# bpq123.net
KiCad netlist of a schematic drawn in Altium Designer
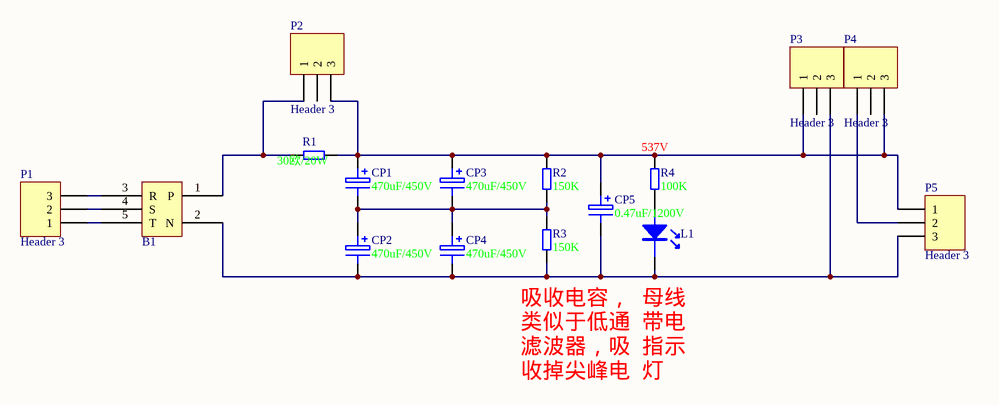
[diagram p0: bpq123.SchDoc]

(export (version "E")
  (design (tool "Eeschema 10.0.6"))
  (components
    (comp (ref "B1")
      (value "3BRIDGE")
      (footprint "cloudlib:三相整流桥")
      (libsource (lib "cloudlib") (part "三相整流桥"))
    )
    (comp (ref "CP1")
      (value "470uF/450V")
      (footprint "cloudlib:CAP_35X50")
      (description "极性电容")
      (libsource (lib "cloudlib") (part "Cap_Pol"))
    )
    (comp (ref "CP2")
      (value "470uF/450V")
      (footprint "cloudlib:CAP_35X50")
      (description "极性电容")
      (libsource (lib "cloudlib") (part "Cap_Pol"))
    )
    (comp (ref "CP3")
      (value "470uF/450V")
      (footprint "cloudlib:CAP_35X50")
      (description "极性电容")
      (libsource (lib "cloudlib") (part "Cap_Pol"))
    )
    (comp (ref "CP4")
      (value "470uF/450V")
      (footprint "cloudlib:CAP_35X50")
      (description "极性电容")
      (libsource (lib "cloudlib") (part "Cap_Pol"))
    )
    (comp (ref "CP5")
      (value "0.47uF/1200V")
      (footprint "myall:CB2")
      (description "极性电容")
      (libsource (lib "cloudlib") (part "Cap_Pol"))
    )
    (comp (ref "L1")
      (value "LED")
      (footprint "LED_1206")
      (description "发光二极管")
      (libsource (lib "cloudlib") (part "LED"))
    )
    (comp (ref "P1")
      (value "Header 3")
      (footprint "cloudlib:30A/300V")
      (description "Header, 3-Pin")
      (fields (field (name "PUBLISHER") "Altium Limited"))
      (libsource (lib "") (part "Header 3_1"))
    )
    (comp (ref "P2")
      (value "Header 3")
      (footprint "cloudlib:30A/300V")
      (description "Header, 3-Pin")
      (fields (field (name "PUBLISHER") "Altium Limited"))
      (libsource (lib "") (part "Header 3_2"))
    )
    (comp (ref "P3")
      (value "Header 3")
      (footprint "cloudlib:5.25-3")
      (description "Header, 3-Pin")
      (fields (field (name "PUBLISHER") "Altium Limited"))
      (libsource (lib "") (part "Header 3_2"))
    )
    (comp (ref "P4")
      (value "Header 3")
      (footprint "cloudlib:5.25-3")
      (description "Header, 3-Pin")
      (fields (field (name "PUBLISHER") "Altium Limited"))
      (libsource (lib "") (part "Header 3_2"))
    )
    (comp (ref "P5")
      (value "Header 3")
      (footprint "cloudlib:30A/300V")
      (description "Header, 3-Pin")
      (fields (field (name "PUBLISHER") "Altium Limited"))
      (libsource (lib "Miscellaneous Connectors") (part "Header 3"))
    )
    (comp (ref "R1")
      (value "30欧/20W")
      (footprint "cloudlib:R_30R/20W")
      (description "电阻")
      (libsource (lib "cloudlib") (part "Res"))
    )
    (comp (ref "R2")
      (value "150K")
      (footprint "myall:AXIAL0.7")
      (description "电阻")
      (libsource (lib "cloudlib") (part "Res"))
    )
    (comp (ref "R3")
      (value "150K")
      (footprint "myall:AXIAL0.7")
      (description "电阻")
      (libsource (lib "cloudlib") (part "Res"))
    )
    (comp (ref "R4")
      (value "100K")
      (footprint "myall:AXIAL0.7")
      (description "电阻")
      (libsource (lib "cloudlib") (part "Res"))
    )
  )
  (nets
    (net (code "1") (name "Net-(B1-N)") (class "Default")
      (node (ref "B1") (pin "2") (pinfunction "N_2") (pintype "passive"))
      (node (ref "CP2") (pin "2") (pinfunction "2_2") (pintype "passive"))
      (node (ref "CP4") (pin "2") (pinfunction "2_2") (pintype "passive"))
      (node (ref "CP5") (pin "2") (pinfunction "2_2") (pintype "passive"))
      (node (ref "L1") (pin "2") (pinfunction "2_2") (pintype "passive"))
      (node (ref "P3") (pin "3") (pinfunction "3_3") (pintype "passive"))
      (node (ref "P5") (pin "3") (pinfunction "3_3") (pintype "passive"))
      (node (ref "R3") (pin "1") (pinfunction "1_1") (pintype "passive"))
    )
    (net (code "2") (name "Net-(B1-P)") (class "Default")
      (node (ref "B1") (pin "1") (pinfunction "P_1") (pintype "passive"))
      (node (ref "P2") (pin "1") (pinfunction "1_1") (pintype "passive"))
      (node (ref "R1") (pin "1") (pinfunction "1_1") (pintype "passive"))
    )
    (net (code "3") (name "Net-(B1-R)") (class "Default")
      (node (ref "B1") (pin "3") (pinfunction "R_3") (pintype "passive"))
      (node (ref "P1") (pin "3") (pinfunction "3_3") (pintype "passive"))
    )
    (net (code "4") (name "Net-(B1-S)") (class "Default")
      (node (ref "B1") (pin "4") (pinfunction "S_4") (pintype "passive"))
      (node (ref "P1") (pin "2") (pinfunction "2_2") (pintype "passive"))
    )
    (net (code "5") (name "Net-(B1-T)") (class "Default")
      (node (ref "B1") (pin "5") (pinfunction "T_5") (pintype "passive"))
      (node (ref "P1") (pin "1") (pinfunction "1_1") (pintype "passive"))
    )
    (net (code "6") (name "Net-(CP1-Pad1)") (class "Default")
      (node (ref "CP1") (pin "1") (pinfunction "1_1") (pintype "passive"))
      (node (ref "CP3") (pin "1") (pinfunction "1_1") (pintype "passive"))
      (node (ref "CP5") (pin "1") (pinfunction "1_1") (pintype "passive"))
      (node (ref "P2") (pin "3") (pinfunction "3_3") (pintype "passive"))
      (node (ref "P3") (pin "1") (pinfunction "1_1") (pintype "passive"))
      (node (ref "P4") (pin "3") (pinfunction "3_3") (pintype "passive"))
      (node (ref "P5") (pin "1") (pinfunction "1_1") (pintype "passive"))
      (node (ref "R1") (pin "2") (pinfunction "2_2") (pintype "passive"))
      (node (ref "R2") (pin "2") (pinfunction "2_2") (pintype "passive"))
      (node (ref "R4") (pin "2") (pinfunction "2_2") (pintype "passive"))
    )
    (net (code "7") (name "Net-(CP1-Pad2)") (class "Default")
      (node (ref "CP1") (pin "2") (pinfunction "2_2") (pintype "passive"))
      (node (ref "CP2") (pin "1") (pinfunction "1_1") (pintype "passive"))
      (node (ref "CP3") (pin "2") (pinfunction "2_2") (pintype "passive"))
      (node (ref "CP4") (pin "1") (pinfunction "1_1") (pintype "passive"))
      (node (ref "R2") (pin "1") (pinfunction "1_1") (pintype "passive"))
      (node (ref "R3") (pin "2") (pinfunction "2_2") (pintype "passive"))
    )
    (net (code "8") (name "Net-(L1-Pad1)") (class "Default")
      (node (ref "L1") (pin "1") (pinfunction "1_1") (pintype "passive"))
      (node (ref "R4") (pin "1") (pinfunction "1_1") (pintype "passive"))
    )
    (net (code "9") (name "Net-(P4-Pad1)") (class "Default")
      (node (ref "P4") (pin "1") (pinfunction "1_1") (pintype "passive"))
      (node (ref "P5") (pin "2") (pinfunction "2_2") (pintype "passive"))
    )
    (net (code "10") (name "unconnected-(P2-Pad2)") (class "Default")
      (node (ref "P2") (pin "2") (pinfunction "2_2") (pintype "passive"))
    )
    (net (code "11") (name "unconnected-(P3-Pad2)") (class "Default")
      (node (ref "P3") (pin "2") (pinfunction "2_2") (pintype "passive"))
    )
    (net (code "12") (name "unconnected-(P4-Pad2)") (class "Default")
      (node (ref "P4") (pin "2") (pinfunction "2_2") (pintype "passive"))
    )
  )
)
